# STM32H743_MCU.net
KiCad netlist of a schematic drawn in Altium Designer
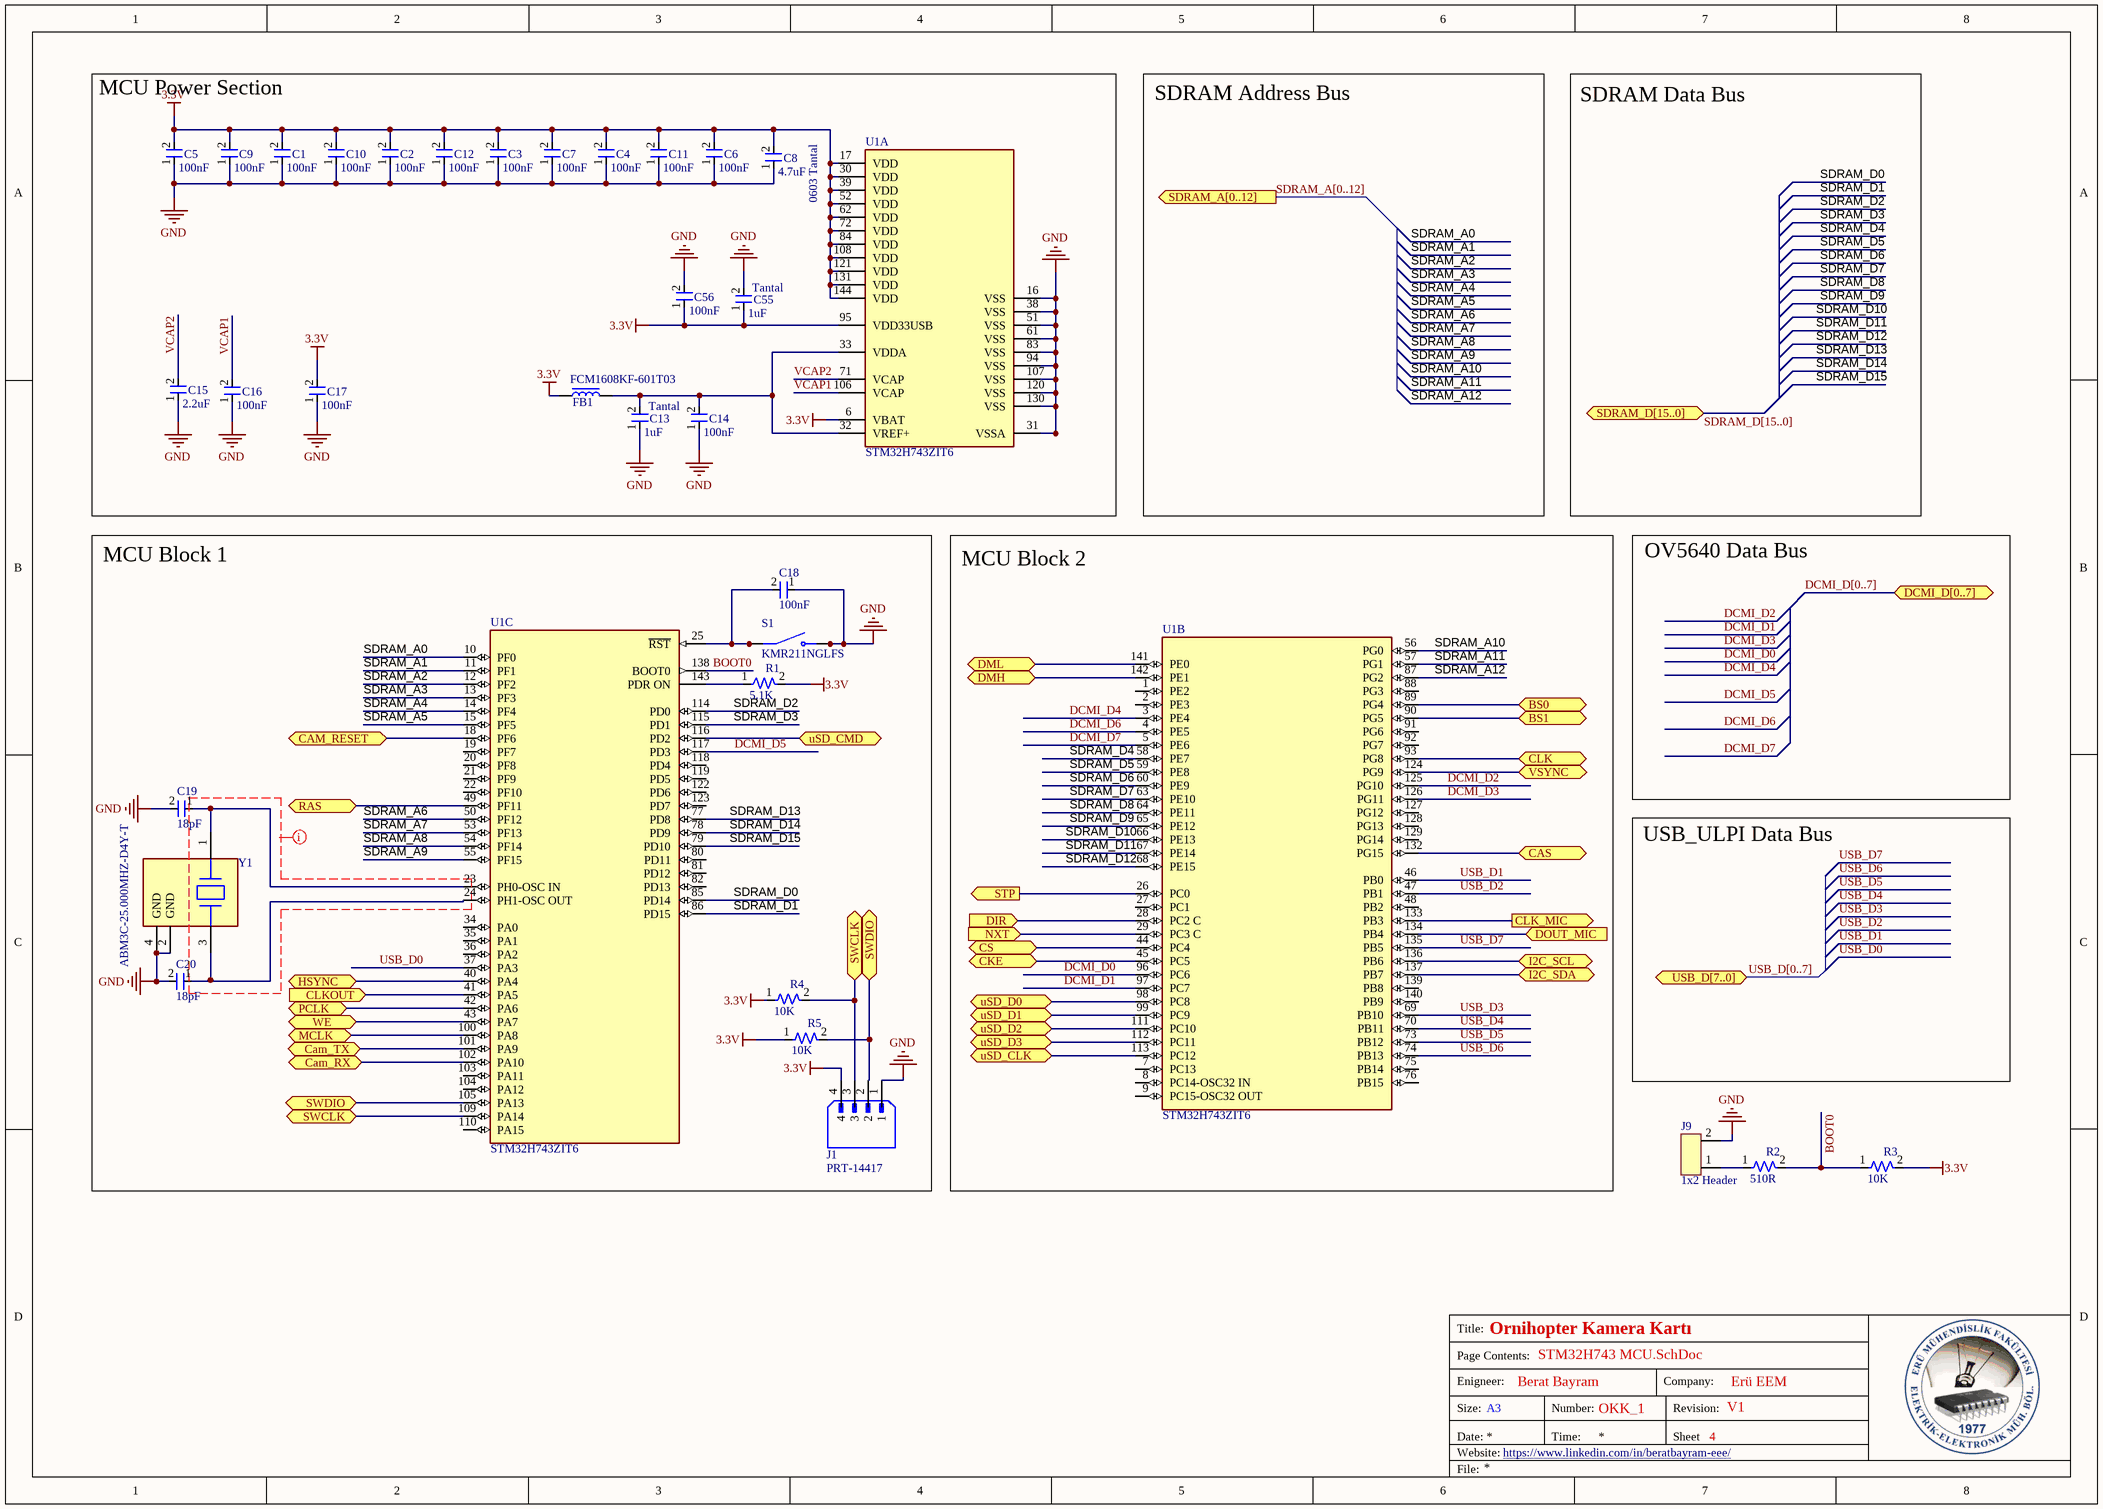
[diagram p0: STM32H743 MCU.SchDoc]

(export (version "E")
  (design (tool "Eeschema 10.0.6"))
  (components
    (comp (ref "C1")
      (value "0603")
      (footprint "0603 Cap")
      (fields (field (name "C") "100nF"))
      (libsource (lib "VoltaRoket") (part "0603 Cap"))
    )
    (comp (ref "C2")
      (value "0603")
      (footprint "0603 Cap")
      (fields (field (name "C") "100nF"))
      (libsource (lib "VoltaRoket") (part "0603 Cap"))
    )
    (comp (ref "C3")
      (value "0603")
      (footprint "0603 Cap")
      (fields (field (name "C") "100nF"))
      (libsource (lib "VoltaRoket") (part "0603 Cap"))
    )
    (comp (ref "C4")
      (value "0603")
      (footprint "0603 Cap")
      (fields (field (name "C") "100nF"))
      (libsource (lib "VoltaRoket") (part "0603 Cap"))
    )
    (comp (ref "C5")
      (value "0603")
      (footprint "0603 Cap")
      (fields (field (name "C") "100nF"))
      (libsource (lib "VoltaRoket") (part "0603 Cap"))
    )
    (comp (ref "C6")
      (value "0603")
      (footprint "0603 Cap")
      (fields (field (name "C") "100nF"))
      (libsource (lib "VoltaRoket") (part "0603 Cap"))
    )
    (comp (ref "C7")
      (value "0603")
      (footprint "0603 Cap")
      (fields (field (name "C") "100nF"))
      (libsource (lib "VoltaRoket") (part "0603 Cap"))
    )
    (comp (ref "C8")
      (value "0603 Tantal")
      (footprint "0603 Cap")
      (fields (field (name "C") "4.7uF"))
      (libsource (lib "VoltaRoket") (part "0603 Cap"))
    )
    (comp (ref "C9")
      (value "0603")
      (footprint "0603 Cap")
      (fields (field (name "C") "100nF"))
      (libsource (lib "VoltaRoket") (part "0603 Cap"))
    )
    (comp (ref "C10")
      (value "0603")
      (footprint "0603 Cap")
      (fields (field (name "C") "100nF"))
      (libsource (lib "VoltaRoket") (part "0603 Cap"))
    )
    (comp (ref "C11")
      (value "0603")
      (footprint "0603 Cap")
      (fields (field (name "C") "100nF"))
      (libsource (lib "VoltaRoket") (part "0603 Cap"))
    )
    (comp (ref "C12")
      (value "0603")
      (footprint "0603 Cap")
      (fields (field (name "C") "100nF"))
      (libsource (lib "VoltaRoket") (part "0603 Cap"))
    )
    (comp (ref "C13")
      (value "Tantal")
      (footprint "0603 Cap")
      (fields (field (name "C") "1uF"))
      (libsource (lib "VoltaRoket") (part "0603 Cap"))
    )
    (comp (ref "C14")
      (value "0603")
      (footprint "0603 Cap")
      (fields (field (name "C") "100nF"))
      (libsource (lib "VoltaRoket") (part "0603 Cap"))
    )
    (comp (ref "C15")
      (value "0603")
      (footprint "0603 Cap")
      (fields (field (name "C") "2.2uF"))
      (libsource (lib "VoltaRoket") (part "0603 Cap"))
    )
    (comp (ref "C16")
      (value "0603")
      (footprint "0603 Cap")
      (fields (field (name "C") "100nF"))
      (libsource (lib "VoltaRoket") (part "0603 Cap"))
    )
    (comp (ref "C17")
      (value "0603")
      (footprint "0603 Cap")
      (fields (field (name "C") "100nF"))
      (libsource (lib "VoltaRoket") (part "0603 Cap"))
    )
    (comp (ref "C18")
      (value "0603")
      (footprint "0603 Cap")
      (fields (field (name "C") "100nF"))
      (libsource (lib "VoltaRoket") (part "0603 Cap"))
    )
    (comp (ref "C19")
      (value "0603")
      (footprint "0603 Cap")
      (fields (field (name "C") "18pF"))
      (libsource (lib "VoltaRoket") (part "0603 Cap"))
    )
    (comp (ref "C20")
      (value "0603")
      (footprint "0603 Cap")
      (fields (field (name "C") "18pF"))
      (libsource (lib "VoltaRoket") (part "0603 Cap"))
    )
    (comp (ref "C55")
      (value "Tantal")
      (footprint "0603 Cap")
      (fields (field (name "C") "1uF"))
      (libsource (lib "VoltaRoket") (part "0603 Cap"))
    )
    (comp (ref "C56")
      (value "0603")
      (footprint "0603 Cap")
      (fields (field (name "C") "100nF"))
      (libsource (lib "VoltaRoket") (part "0603 Cap"))
    )
    (comp (ref "FB1")
      (value "FCM1608KF-601T03")
      (footprint "FB_0603")
      (description "Ferrite Bead SMD 0603")
      (libsource (lib "Phills_Lib") (part "FB_0603"))
    )
    (comp (ref "J1")
      (value "PRT-14417")
      (footprint "SPARKFUN_PRT-14417")
      (description "QWIIC JST CONNECTOR - SMD 4-PIN")
      (fields (field (name "MF") "SparkFun Electronics"))
      (libsource (lib "PRT-14417 (1)") (part "PRT-14417"))
    )
    (comp (ref "J9")
      (value "1x2 Header")
      (footprint "1x2 Header")
      (libsource (lib "VoltaRoket") (part "1x2 Header"))
    )
    (comp (ref "R1")
      (value "0603")
      (footprint "0603 Res")
      (fields (field (name "R") "5.1K"))
      (libsource (lib "VoltaRoket") (part "0603 Res"))
    )
    (comp (ref "R2")
      (value "0603")
      (footprint "0603 Res")
      (fields (field (name "R") "510R"))
      (libsource (lib "VoltaRoket") (part "0603 Res"))
    )
    (comp (ref "R3")
      (value "0603")
      (footprint "0603 Res")
      (fields (field (name "R") "10K"))
      (libsource (lib "VoltaRoket") (part "0603 Res"))
    )
    (comp (ref "R4")
      (value "0603")
      (footprint "0603 Res")
      (fields (field (name "R") "10K"))
      (libsource (lib "VoltaRoket") (part "0603 Res"))
    )
    (comp (ref "R5")
      (value "0603")
      (footprint "0603 Res")
      (fields (field (name "R") "10K"))
      (libsource (lib "VoltaRoket") (part "0603 Res"))
    )
    (comp (ref "S1")
      (value "KMR211NGLFS")
      (footprint "SW_KMR211NGLFS")
      (description "Tactile Switch SPST-NO Top Actuated Surface Mount")
      (fields (field (name "MF") "C&K Components"))
      (libsource (lib "KMR211NGLFS") (part "KMR211NGLFS"))
    )
    (comp (ref "U1")
      (value "STM32H743ZIT6")
      (footprint "FP-LQFP144-1A-MFG")
      (description "IC MCU 32BIT 2MB FLASH 144LQFP")
      (fields
        (field (name "MANUFACTURER") "STMicroelectronics")
        (field (name "OCTOPART") "https://octopart.com/stm32h743zit6-stmicroelectronics-76372529")
      )
      (libsource (lib "Altium Content Vault") (part "4977c5c7f8d170b58ef15f889e64ba1"))
    )
    (comp (ref "Y1")
      (value "ABM3C-25.000MHZ-D4Y-T")
      (footprint "FP-ABM3C-MFG")
      (description "Crystal 25MHz ±30ppm 18pF SMD-4 5mm x 3.2mm")
      (fields (field (name "TOLERANCE") "30ppm"))
      (libsource (lib "Altium Content Vault") (part "48e526d86b7f2615d98721063c72f49"))
    )
  )
  (nets
    (net (code "1") (name "/BOOT0") (class "Default")
      (node (ref "R2") (pin "2") (pinfunction "2_2") (pintype "passive"))
      (node (ref "R3") (pin "1") (pinfunction "1_1") (pintype "passive"))
      (node (ref "U1") (pin "138") (pinfunction "BOOT0_138") (pintype "output"))
    )
    (net (code "2") (name "/BS0") (class "Default")
      (node (ref "U1") (pin "89") (pinfunction "PG4_89") (pintype "bidirectional"))
    )
    (net (code "3") (name "/BS1") (class "Default")
      (node (ref "U1") (pin "90") (pinfunction "PG5_90") (pintype "bidirectional"))
    )
    (net (code "4") (name "/CAM_RESET") (class "Default")
      (node (ref "U1") (pin "18") (pinfunction "PF6_18") (pintype "bidirectional"))
    )
    (net (code "5") (name "/CAS") (class "Default")
      (node (ref "U1") (pin "132") (pinfunction "PG15_132") (pintype "bidirectional"))
    )
    (net (code "6") (name "/CKE") (class "Default")
      (node (ref "U1") (pin "45") (pinfunction "PC5_45") (pintype "bidirectional"))
    )
    (net (code "7") (name "/CLK") (class "Default")
      (node (ref "U1") (pin "93") (pinfunction "PG8_93") (pintype "bidirectional"))
    )
    (net (code "8") (name "/CLKOUT") (class "Default")
      (node (ref "U1") (pin "41") (pinfunction "PA5_41") (pintype "bidirectional"))
    )
    (net (code "9") (name "/CLK_MIC") (class "Default")
      (node (ref "U1") (pin "133") (pinfunction "PB3_133") (pintype "bidirectional"))
    )
    (net (code "10") (name "/CS") (class "Default")
      (node (ref "U1") (pin "44") (pinfunction "PC4_44") (pintype "bidirectional"))
    )
    (net (code "11") (name "/Cam_RX") (class "Default")
      (node (ref "U1") (pin "102") (pinfunction "PA10_102") (pintype "bidirectional"))
    )
    (net (code "12") (name "/Cam_TX") (class "Default")
      (node (ref "U1") (pin "101") (pinfunction "PA9_101") (pintype "bidirectional"))
    )
    (net (code "13") (name "/DCMI_D0") (class "Default")
      (node (ref "U1") (pin "96") (pinfunction "PC6_96") (pintype "bidirectional"))
    )
    (net (code "14") (name "/DCMI_D1") (class "Default")
      (node (ref "U1") (pin "97") (pinfunction "PC7_97") (pintype "bidirectional"))
    )
    (net (code "15") (name "/DCMI_D2") (class "Default")
      (node (ref "U1") (pin "125") (pinfunction "PG10_125") (pintype "bidirectional"))
    )
    (net (code "16") (name "/DCMI_D3") (class "Default")
      (node (ref "U1") (pin "126") (pinfunction "PG11_126") (pintype "bidirectional"))
    )
    (net (code "17") (name "/DCMI_D4") (class "Default")
      (node (ref "U1") (pin "3") (pinfunction "PE4_3") (pintype "bidirectional"))
    )
    (net (code "18") (name "/DCMI_D5") (class "Default")
      (node (ref "U1") (pin "117") (pinfunction "PD3_117") (pintype "bidirectional"))
    )
    (net (code "19") (name "/DCMI_D6") (class "Default")
      (node (ref "U1") (pin "4") (pinfunction "PE5_4") (pintype "bidirectional"))
    )
    (net (code "20") (name "/DCMI_D7") (class "Default")
      (node (ref "U1") (pin "5") (pinfunction "PE6_5") (pintype "bidirectional"))
    )
    (net (code "22") (name "/DIR") (class "Default")
      (node (ref "U1") (pin "28") (pinfunction "PC2_C_28") (pintype "bidirectional"))
    )
    (net (code "23") (name "/DMH") (class "Default")
      (node (ref "U1") (pin "142") (pinfunction "PE1_142") (pintype "bidirectional"))
    )
    (net (code "24") (name "/DML") (class "Default")
      (node (ref "U1") (pin "141") (pinfunction "PE0_141") (pintype "bidirectional"))
    )
    (net (code "25") (name "/DOUT_MIC") (class "Default")
      (node (ref "U1") (pin "134") (pinfunction "PB4_134") (pintype "bidirectional"))
    )
    (net (code "26") (name "/HSYNC") (class "Default")
      (node (ref "U1") (pin "40") (pinfunction "PA4_40") (pintype "bidirectional"))
    )
    (net (code "27") (name "/I2C_SCL") (class "Default")
      (node (ref "U1") (pin "136") (pinfunction "PB6_136") (pintype "bidirectional"))
    )
    (net (code "28") (name "/I2C_SDA") (class "Default")
      (node (ref "U1") (pin "137") (pinfunction "PB7_137") (pintype "bidirectional"))
    )
    (net (code "29") (name "/MCLK") (class "Default")
      (node (ref "U1") (pin "100") (pinfunction "PA8_100") (pintype "bidirectional"))
    )
    (net (code "30") (name "/NXT") (class "Default")
      (node (ref "U1") (pin "29") (pinfunction "PC3_C_29") (pintype "bidirectional"))
    )
    (net (code "31") (name "/PCLK") (class "Default")
      (node (ref "U1") (pin "42") (pinfunction "PA6_42") (pintype "bidirectional"))
    )
    (net (code "32") (name "/RAS") (class "Default")
      (node (ref "U1") (pin "49") (pinfunction "PF11_49") (pintype "bidirectional"))
    )
    (net (code "33") (name "/SDRAM_A0") (class "Default")
      (node (ref "U1") (pin "10") (pinfunction "PF0_10") (pintype "bidirectional"))
    )
    (net (code "34") (name "/SDRAM_A1") (class "Default")
      (node (ref "U1") (pin "11") (pinfunction "PF1_11") (pintype "bidirectional"))
    )
    (net (code "35") (name "/SDRAM_A2") (class "Default")
      (node (ref "U1") (pin "12") (pinfunction "PF2_12") (pintype "bidirectional"))
    )
    (net (code "36") (name "/SDRAM_A3") (class "Default")
      (node (ref "U1") (pin "13") (pinfunction "PF3_13") (pintype "bidirectional"))
    )
    (net (code "37") (name "/SDRAM_A4") (class "Default")
      (node (ref "U1") (pin "14") (pinfunction "PF4_14") (pintype "bidirectional"))
    )
    (net (code "38") (name "/SDRAM_A5") (class "Default")
      (node (ref "U1") (pin "15") (pinfunction "PF5_15") (pintype "bidirectional"))
    )
    (net (code "39") (name "/SDRAM_A6") (class "Default")
      (node (ref "U1") (pin "50") (pinfunction "PF12_50") (pintype "bidirectional"))
    )
    (net (code "40") (name "/SDRAM_A7") (class "Default")
      (node (ref "U1") (pin "53") (pinfunction "PF13_53") (pintype "bidirectional"))
    )
    (net (code "41") (name "/SDRAM_A8") (class "Default")
      (node (ref "U1") (pin "54") (pinfunction "PF14_54") (pintype "bidirectional"))
    )
    (net (code "42") (name "/SDRAM_A9") (class "Default")
      (node (ref "U1") (pin "55") (pinfunction "PF15_55") (pintype "bidirectional"))
    )
    (net (code "43") (name "/SDRAM_A10") (class "Default")
      (node (ref "U1") (pin "56") (pinfunction "PG0_56") (pintype "bidirectional"))
    )
    (net (code "44") (name "/SDRAM_A11") (class "Default")
      (node (ref "U1") (pin "57") (pinfunction "PG1_57") (pintype "bidirectional"))
    )
    (net (code "45") (name "/SDRAM_A12") (class "Default")
      (node (ref "U1") (pin "87") (pinfunction "PG2_87") (pintype "bidirectional"))
    )
    (net (code "47") (name "/SDRAM_D0") (class "Default")
      (node (ref "U1") (pin "85") (pinfunction "PD14_85") (pintype "bidirectional"))
    )
    (net (code "48") (name "/SDRAM_D1") (class "Default")
      (node (ref "U1") (pin "86") (pinfunction "PD15_86") (pintype "bidirectional"))
    )
    (net (code "49") (name "/SDRAM_D2") (class "Default")
      (node (ref "U1") (pin "114") (pinfunction "PD0_114") (pintype "bidirectional"))
    )
    (net (code "50") (name "/SDRAM_D3") (class "Default")
      (node (ref "U1") (pin "115") (pinfunction "PD1_115") (pintype "bidirectional"))
    )
    (net (code "51") (name "/SDRAM_D4") (class "Default")
      (node (ref "U1") (pin "58") (pinfunction "PE7_58") (pintype "bidirectional"))
    )
    (net (code "52") (name "/SDRAM_D5") (class "Default")
      (node (ref "U1") (pin "59") (pinfunction "PE8_59") (pintype "bidirectional"))
    )
    (net (code "53") (name "/SDRAM_D6") (class "Default")
      (node (ref "U1") (pin "60") (pinfunction "PE9_60") (pintype "bidirectional"))
    )
    (net (code "54") (name "/SDRAM_D7") (class "Default")
      (node (ref "U1") (pin "63") (pinfunction "PE10_63") (pintype "bidirectional"))
    )
    (net (code "55") (name "/SDRAM_D8") (class "Default")
      (node (ref "U1") (pin "64") (pinfunction "PE11_64") (pintype "bidirectional"))
    )
    (net (code "56") (name "/SDRAM_D9") (class "Default")
      (node (ref "U1") (pin "65") (pinfunction "PE12_65") (pintype "bidirectional"))
    )
    (net (code "57") (name "/SDRAM_D10") (class "Default")
      (node (ref "U1") (pin "66") (pinfunction "PE13_66") (pintype "bidirectional"))
    )
    (net (code "58") (name "/SDRAM_D11") (class "Default")
      (node (ref "U1") (pin "67") (pinfunction "PE14_67") (pintype "bidirectional"))
    )
    (net (code "59") (name "/SDRAM_D12") (class "Default")
      (node (ref "U1") (pin "68") (pinfunction "PE15_68") (pintype "bidirectional"))
    )
    (net (code "60") (name "/SDRAM_D13") (class "Default")
      (node (ref "U1") (pin "77") (pinfunction "PD8_77") (pintype "bidirectional"))
    )
    (net (code "61") (name "/SDRAM_D14") (class "Default")
      (node (ref "U1") (pin "78") (pinfunction "PD9_78") (pintype "bidirectional"))
    )
    (net (code "62") (name "/SDRAM_D15") (class "Default")
      (node (ref "U1") (pin "79") (pinfunction "PD10_79") (pintype "bidirectional"))
    )
    (net (code "64") (name "/STP") (class "Default")
      (node (ref "U1") (pin "26") (pinfunction "PC0_26") (pintype "bidirectional"))
    )
    (net (code "65") (name "/SWCLK") (class "Default")
      (node (ref "J1") (pin "3") (pinfunction "3_3") (pintype "passive"))
      (node (ref "R4") (pin "2") (pinfunction "2_2") (pintype "passive"))
      (node (ref "U1") (pin "109") (pinfunction "PA14_109") (pintype "bidirectional"))
    )
    (net (code "66") (name "/SWDIO") (class "Default")
      (node (ref "J1") (pin "2") (pinfunction "2_2") (pintype "passive"))
      (node (ref "R5") (pin "2") (pinfunction "2_2") (pintype "passive"))
      (node (ref "U1") (pin "105") (pinfunction "PA13_105") (pintype "bidirectional"))
    )
    (net (code "67") (name "/USB_D0") (class "Default")
      (node (ref "U1") (pin "37") (pinfunction "PA3_37") (pintype "bidirectional"))
    )
    (net (code "68") (name "/USB_D1") (class "Default")
      (node (ref "U1") (pin "46") (pinfunction "PB0_46") (pintype "bidirectional"))
    )
    (net (code "69") (name "/USB_D2") (class "Default")
      (node (ref "U1") (pin "47") (pinfunction "PB1_47") (pintype "bidirectional"))
    )
    (net (code "70") (name "/USB_D3") (class "Default")
      (node (ref "U1") (pin "69") (pinfunction "PB10_69") (pintype "bidirectional"))
    )
    (net (code "71") (name "/USB_D4") (class "Default")
      (node (ref "U1") (pin "70") (pinfunction "PB11_70") (pintype "bidirectional"))
    )
    (net (code "72") (name "/USB_D5") (class "Default")
      (node (ref "U1") (pin "73") (pinfunction "PB12_73") (pintype "bidirectional"))
    )
    (net (code "73") (name "/USB_D6") (class "Default")
      (node (ref "U1") (pin "74") (pinfunction "PB13_74") (pintype "bidirectional"))
    )
    (net (code "74") (name "/USB_D7") (class "Default")
      (node (ref "U1") (pin "135") (pinfunction "PB5_135") (pintype "bidirectional"))
    )
    (net (code "76") (name "/VCAP1") (class "Default")
      (node (ref "C16") (pin "2") (pinfunction "2_2") (pintype "passive"))
      (node (ref "U1") (pin "106") (pinfunction "VCAP_106") (pintype "power_in"))
    )
    (net (code "77") (name "/VCAP2") (class "Default")
      (node (ref "C15") (pin "2") (pinfunction "2_2") (pintype "passive"))
      (node (ref "U1") (pin "71") (pinfunction "VCAP_71") (pintype "power_in"))
    )
    (net (code "78") (name "/VSYNC") (class "Default")
      (node (ref "U1") (pin "124") (pinfunction "PG9_124") (pintype "bidirectional"))
    )
    (net (code "79") (name "/WE") (class "Default")
      (node (ref "U1") (pin "43") (pinfunction "PA7_43") (pintype "bidirectional"))
    )
    (net (code "80") (name "/uSD_CLK") (class "Default")
      (node (ref "U1") (pin "113") (pinfunction "PC12_113") (pintype "bidirectional"))
    )
    (net (code "81") (name "/uSD_CMD") (class "Default")
      (node (ref "U1") (pin "116") (pinfunction "PD2_116") (pintype "bidirectional"))
    )
    (net (code "82") (name "/uSD_D0") (class "Default")
      (node (ref "U1") (pin "98") (pinfunction "PC8_98") (pintype "bidirectional"))
    )
    (net (code "83") (name "/uSD_D1") (class "Default")
      (node (ref "U1") (pin "99") (pinfunction "PC9_99") (pintype "bidirectional"))
    )
    (net (code "84") (name "/uSD_D2") (class "Default")
      (node (ref "U1") (pin "111") (pinfunction "PC10_111") (pintype "bidirectional"))
    )
    (net (code "85") (name "/uSD_D3") (class "Default")
      (node (ref "U1") (pin "112") (pinfunction "PC11_112") (pintype "bidirectional"))
    )
    (net (code "86") (name "3.3V") (class "Default")
      (node (ref "C1") (pin "2") (pinfunction "2_2") (pintype "passive"))
      (node (ref "C10") (pin "2") (pinfunction "2_2") (pintype "passive"))
      (node (ref "C11") (pin "2") (pinfunction "2_2") (pintype "passive"))
      (node (ref "C12") (pin "2") (pinfunction "2_2") (pintype "passive"))
      (node (ref "C17") (pin "2") (pinfunction "2_2") (pintype "passive"))
      (node (ref "C2") (pin "2") (pinfunction "2_2") (pintype "passive"))
      (node (ref "C3") (pin "2") (pinfunction "2_2") (pintype "passive"))
      (node (ref "C4") (pin "2") (pinfunction "2_2") (pintype "passive"))
      (node (ref "C5") (pin "2") (pinfunction "2_2") (pintype "passive"))
      (node (ref "C55") (pin "1") (pinfunction "1_1") (pintype "passive"))
      (node (ref "C56") (pin "1") (pinfunction "1_1") (pintype "passive"))
      (node (ref "C6") (pin "2") (pinfunction "2_2") (pintype "passive"))
      (node (ref "C7") (pin "2") (pinfunction "2_2") (pintype "passive"))
      (node (ref "C8") (pin "2") (pinfunction "2_2") (pintype "passive"))
      (node (ref "C9") (pin "2") (pinfunction "2_2") (pintype "passive"))
      (node (ref "FB1") (pin "1") (pinfunction "1_1") (pintype "passive"))
      (node (ref "J1") (pin "4") (pinfunction "4_4") (pintype "passive"))
      (node (ref "R1") (pin "2") (pinfunction "2_2") (pintype "passive"))
      (node (ref "R3") (pin "2") (pinfunction "2_2") (pintype "passive"))
      (node (ref "R4") (pin "1") (pinfunction "1_1") (pintype "passive"))
      (node (ref "R5") (pin "1") (pinfunction "1_1") (pintype "passive"))
      (node (ref "U1") (pin "108") (pinfunction "VDD_108") (pintype "power_in"))
      (node (ref "U1") (pin "121") (pinfunction "VDD_121") (pintype "power_in"))
      (node (ref "U1") (pin "131") (pinfunction "VDD_131") (pintype "power_in"))
      (node (ref "U1") (pin "144") (pinfunction "VDD_144") (pintype "power_in"))
      (node (ref "U1") (pin "17") (pinfunction "VDD_17") (pintype "power_in"))
      (node (ref "U1") (pin "30") (pinfunction "VDD_30") (pintype "power_in"))
      (node (ref "U1") (pin "39") (pinfunction "VDD_39") (pintype "power_in"))
      (node (ref "U1") (pin "52") (pinfunction "VDD_52") (pintype "power_in"))
      (node (ref "U1") (pin "6") (pinfunction "VBAT_6") (pintype "power_in"))
      (node (ref "U1") (pin "62") (pinfunction "VDD_62") (pintype "power_in"))
      (node (ref "U1") (pin "72") (pinfunction "VDD_72") (pintype "power_in"))
      (node (ref "U1") (pin "84") (pinfunction "VDD_84") (pintype "power_in"))
      (node (ref "U1") (pin "95") (pinfunction "VDD33USB_95") (pintype "power_in"))
    )
    (net (code "87") (name "GND") (class "Default")
      (node (ref "C1") (pin "1") (pinfunction "1_1") (pintype "passive"))
      (node (ref "C10") (pin "1") (pinfunction "1_1") (pintype "passive"))
      (node (ref "C11") (pin "1") (pinfunction "1_1") (pintype "passive"))
      (node (ref "C12") (pin "1") (pinfunction "1_1") (pintype "passive"))
      (node (ref "C13") (pin "1") (pinfunction "1_1") (pintype "passive"))
      (node (ref "C14") (pin "1") (pinfunction "1_1") (pintype "passive"))
      (node (ref "C15") (pin "1") (pinfunction "1_1") (pintype "passive"))
      (node (ref "C16") (pin "1") (pinfunction "1_1") (pintype "passive"))
      (node (ref "C17") (pin "1") (pinfunction "1_1") (pintype "passive"))
      (node (ref "C18") (pin "1") (pinfunction "1_1") (pintype "passive"))
      (node (ref "C19") (pin "2") (pinfunction "2_2") (pintype "passive"))
      (node (ref "C2") (pin "1") (pinfunction "1_1") (pintype "passive"))
      (node (ref "C20") (pin "2") (pinfunction "2_2") (pintype "passive"))
      (node (ref "C3") (pin "1") (pinfunction "1_1") (pintype "passive"))
      (node (ref "C4") (pin "1") (pinfunction "1_1") (pintype "passive"))
      (node (ref "C5") (pin "1") (pinfunction "1_1") (pintype "passive"))
      (node (ref "C55") (pin "2") (pinfunction "2_2") (pintype "passive"))
      (node (ref "C56") (pin "2") (pinfunction "2_2") (pintype "passive"))
      (node (ref "C6") (pin "1") (pinfunction "1_1") (pintype "passive"))
      (node (ref "C7") (pin "1") (pinfunction "1_1") (pintype "passive"))
      (node (ref "C8") (pin "1") (pinfunction "1_1") (pintype "passive"))
      (node (ref "C9") (pin "1") (pinfunction "1_1") (pintype "passive"))
      (node (ref "J1") (pin "1") (pinfunction "1_1") (pintype "passive"))
      (node (ref "J9") (pin "2") (pinfunction "2_2") (pintype "passive"))
      (node (ref "S1") (pin "3") (pinfunction "NO_3") (pintype "passive"))
      (node (ref "S1") (pin "4") (pinfunction "NO_4") (pintype "passive"))
      (node (ref "U1") (pin "107") (pinfunction "VSS_107") (pintype "power_in"))
      (node (ref "U1") (pin "120") (pinfunction "VSS_120") (pintype "power_in"))
      (node (ref "U1") (pin "130") (pinfunction "VSS_130") (pintype "power_in"))
      (node (ref "U1") (pin "16") (pinfunction "VSS_16") (pintype "power_in"))
      (node (ref "U1") (pin "31") (pinfunction "VSSA_31") (pintype "power_in"))
      (node (ref "U1") (pin "38") (pinfunction "VSS_38") (pintype "power_in"))
      (node (ref "U1") (pin "51") (pinfunction "VSS_51") (pintype "power_in"))
      (node (ref "U1") (pin "61") (pinfunction "VSS_61") (pintype "power_in"))
      (node (ref "U1") (pin "83") (pinfunction "VSS_83") (pintype "power_in"))
      (node (ref "U1") (pin "94") (pinfunction "VSS_94") (pintype "power_in"))
      (node (ref "Y1") (pin "2") (pinfunction "GND_2") (pintype "power_in"))
      (node (ref "Y1") (pin "4") (pinfunction "GND_4") (pintype "power_in"))
    )
    (net (code "88") (name "Net-(J9-Pad1)") (class "Default")
      (node (ref "J9") (pin "1") (pinfunction "1_1") (pintype "passive"))
      (node (ref "R2") (pin "1") (pinfunction "1_1") (pintype "passive"))
    )
    (net (code "89") (name "Net-(U1A-VDDA)") (class "Default")
      (node (ref "C13") (pin "2") (pinfunction "2_2") (pintype "passive"))
      (node (ref "C14") (pin "2") (pinfunction "2_2") (pintype "passive"))
      (node (ref "FB1") (pin "2") (pinfunction "2_2") (pintype "passive"))
      (node (ref "U1") (pin "32") (pinfunction "VREF+_32") (pintype "power_in"))
      (node (ref "U1") (pin "33") (pinfunction "VDDA_33") (pintype "power_in"))
    )
    (net (code "90") (name "Net-(U1C-PDR_ON)") (class "Default")
      (node (ref "R1") (pin "1") (pinfunction "1_1") (pintype "passive"))
      (node (ref "U1") (pin "143") (pinfunction "PDR_ON_143") (pintype "power_in"))
    )
    (net (code "91") (name "Net-(U1C-PH0-OSC_IN)") (class "Default")
      (node (ref "C19") (pin "1") (pinfunction "1_1") (pintype "passive"))
      (node (ref "U1") (pin "23") (pinfunction "PH0-OSC_IN_23") (pintype "bidirectional"))
      (node (ref "Y1") (pin "1") (pinfunction "1_1") (pintype "passive"))
    )
    (net (code "92") (name "Net-(U1C-PH1-OSC_OUT)") (class "Default")
      (node (ref "C20") (pin "1") (pinfunction "1_1") (pintype "passive"))
      (node (ref "U1") (pin "24") (pinfunction "PH1-OSC_OUT_24") (pintype "bidirectional"))
      (node (ref "Y1") (pin "3") (pinfunction "3_3") (pintype "passive"))
    )
    (net (code "93") (name "Net-(U1C-~{RST})") (class "Default")
      (node (ref "C18") (pin "2") (pinfunction "2_2") (pintype "passive"))
      (node (ref "S1") (pin "1") (pinfunction "COM_1") (pintype "passive"))
      (node (ref "S1") (pin "2") (pinfunction "COM_2") (pintype "passive"))
      (node (ref "U1") (pin "25") (pinfunction "~{RST}_25") (pintype "input"))
    )
    (net (code "94") (name "unconnected-(U1B-PB2-Pad48)") (class "Default")
      (node (ref "U1") (pin "48") (pinfunction "PB2_48") (pintype "bidirectional"))
    )
    (net (code "95") (name "unconnected-(U1B-PB8-Pad139)") (class "Default")
      (node (ref "U1") (pin "139") (pinfunction "PB8_139") (pintype "bidirectional"))
    )
    (net (code "96") (name "unconnected-(U1B-PB9-Pad140)") (class "Default")
      (node (ref "U1") (pin "140") (pinfunction "PB9_140") (pintype "bidirectional"))
    )
    (net (code "97") (name "unconnected-(U1B-PB14-Pad75)") (class "Default")
      (node (ref "U1") (pin "75") (pinfunction "PB14_75") (pintype "bidirectional"))
    )
    (net (code "98") (name "unconnected-(U1B-PB15-Pad76)") (class "Default")
      (node (ref "U1") (pin "76") (pinfunction "PB15_76") (pintype "bidirectional"))
    )
    (net (code "99") (name "unconnected-(U1B-PC1-Pad27)") (class "Default")
      (node (ref "U1") (pin "27") (pinfunction "PC1_27") (pintype "bidirectional"))
    )
    (net (code "100") (name "unconnected-(U1B-PC13-Pad7)") (class "Default")
      (node (ref "U1") (pin "7") (pinfunction "PC13_7") (pintype "bidirectional"))
    )
    (net (code "101") (name "unconnected-(U1B-PC14-OSC32_IN-Pad8)") (class "Default")
      (node (ref "U1") (pin "8") (pinfunction "PC14-OSC32_IN_8") (pintype "bidirectional"))
    )
    (net (code "102") (name "unconnected-(U1B-PC15-OSC32_OUT-Pad9)") (class "Default")
      (node (ref "U1") (pin "9") (pinfunction "PC15-OSC32_OUT_9") (pintype "bidirectional"))
    )
    (net (code "103") (name "unconnected-(U1B-PE2-Pad1)") (class "Default")
      (node (ref "U1") (pin "1") (pinfunction "PE2_1") (pintype "bidirectional"))
    )
    (net (code "104") (name "unconnected-(U1B-PE3-Pad2)") (class "Default")
      (node (ref "U1") (pin "2") (pinfunction "PE3_2") (pintype "bidirectional"))
    )
    (net (code "105") (name "unconnected-(U1B-PG3-Pad88)") (class "Default")
      (node (ref "U1") (pin "88") (pinfunction "PG3_88") (pintype "bidirectional"))
    )
    (net (code "106") (name "unconnected-(U1B-PG6-Pad91)") (class "Default")
      (node (ref "U1") (pin "91") (pinfunction "PG6_91") (pintype "bidirectional"))
    )
    (net (code "107") (name "unconnected-(U1B-PG7-Pad92)") (class "Default")
      (node (ref "U1") (pin "92") (pinfunction "PG7_92") (pintype "bidirectional"))
    )
    (net (code "108") (name "unconnected-(U1B-PG12-Pad127)") (class "Default")
      (node (ref "U1") (pin "127") (pinfunction "PG12_127") (pintype "bidirectional"))
    )
    (net (code "109") (name "unconnected-(U1B-PG13-Pad128)") (class "Default")
      (node (ref "U1") (pin "128") (pinfunction "PG13_128") (pintype "bidirectional"))
    )
    (net (code "110") (name "unconnected-(U1B-PG14-Pad129)") (class "Default")
      (node (ref "U1") (pin "129") (pinfunction "PG14_129") (pintype "bidirectional"))
    )
    (net (code "111") (name "unconnected-(U1C-PA0-Pad34)") (class "Default")
      (node (ref "U1") (pin "34") (pinfunction "PA0_34") (pintype "bidirectional"))
    )
    (net (code "112") (name "unconnected-(U1C-PA1-Pad35)") (class "Default")
      (node (ref "U1") (pin "35") (pinfunction "PA1_35") (pintype "bidirectional"))
    )
    (net (code "113") (name "unconnected-(U1C-PA2-Pad36)") (class "Default")
      (node (ref "U1") (pin "36") (pinfunction "PA2_36") (pintype "bidirectional"))
    )
    (net (code "114") (name "unconnected-(U1C-PA11-Pad103)") (class "Default")
      (node (ref "U1") (pin "103") (pinfunction "PA11_103") (pintype "bidirectional"))
    )
    (net (code "115") (name "unconnected-(U1C-PA12-Pad104)") (class "Default")
      (node (ref "U1") (pin "104") (pinfunction "PA12_104") (pintype "bidirectional"))
    )
    (net (code "116") (name "unconnected-(U1C-PA15-Pad110)") (class "Default")
      (node (ref "U1") (pin "110") (pinfunction "PA15_110") (pintype "bidirectional"))
    )
    (net (code "117") (name "unconnected-(U1C-PD4-Pad118)") (class "Default")
      (node (ref "U1") (pin "118") (pinfunction "PD4_118") (pintype "bidirectional"))
    )
    (net (code "118") (name "unconnected-(U1C-PD5-Pad119)") (class "Default")
      (node (ref "U1") (pin "119") (pinfunction "PD5_119") (pintype "bidirectional"))
    )
    (net (code "119") (name "unconnected-(U1C-PD6-Pad122)") (class "Default")
      (node (ref "U1") (pin "122") (pinfunction "PD6_122") (pintype "bidirectional"))
    )
    (net (code "120") (name "unconnected-(U1C-PD7-Pad123)") (class "Default")
      (node (ref "U1") (pin "123") (pinfunction "PD7_123") (pintype "bidirectional"))
    )
    (net (code "121") (name "unconnected-(U1C-PD11-Pad80)") (class "Default")
      (node (ref "U1") (pin "80") (pinfunction "PD11_80") (pintype "bidirectional"))
    )
    (net (code "122") (name "unconnected-(U1C-PD12-Pad81)") (class "Default")
      (node (ref "U1") (pin "81") (pinfunction "PD12_81") (pintype "bidirectional"))
    )
    (net (code "123") (name "unconnected-(U1C-PD13-Pad82)") (class "Default")
      (node (ref "U1") (pin "82") (pinfunction "PD13_82") (pintype "bidirectional"))
    )
    (net (code "124") (name "unconnected-(U1C-PF7-Pad19)") (class "Default")
      (node (ref "U1") (pin "19") (pinfunction "PF7_19") (pintype "bidirectional"))
    )
    (net (code "125") (name "unconnected-(U1C-PF8-Pad20)") (class "Default")
      (node (ref "U1") (pin "20") (pinfunction "PF8_20") (pintype "bidirectional"))
    )
    (net (code "126") (name "unconnected-(U1C-PF9-Pad21)") (class "Default")
      (node (ref "U1") (pin "21") (pinfunction "PF9_21") (pintype "bidirectional"))
    )
    (net (code "127") (name "unconnected-(U1C-PF10-Pad22)") (class "Default")
      (node (ref "U1") (pin "22") (pinfunction "PF10_22") (pintype "bidirectional"))
    )
  )
)
